# power.net
KiCad netlist of a schematic drawn in Altium Designer
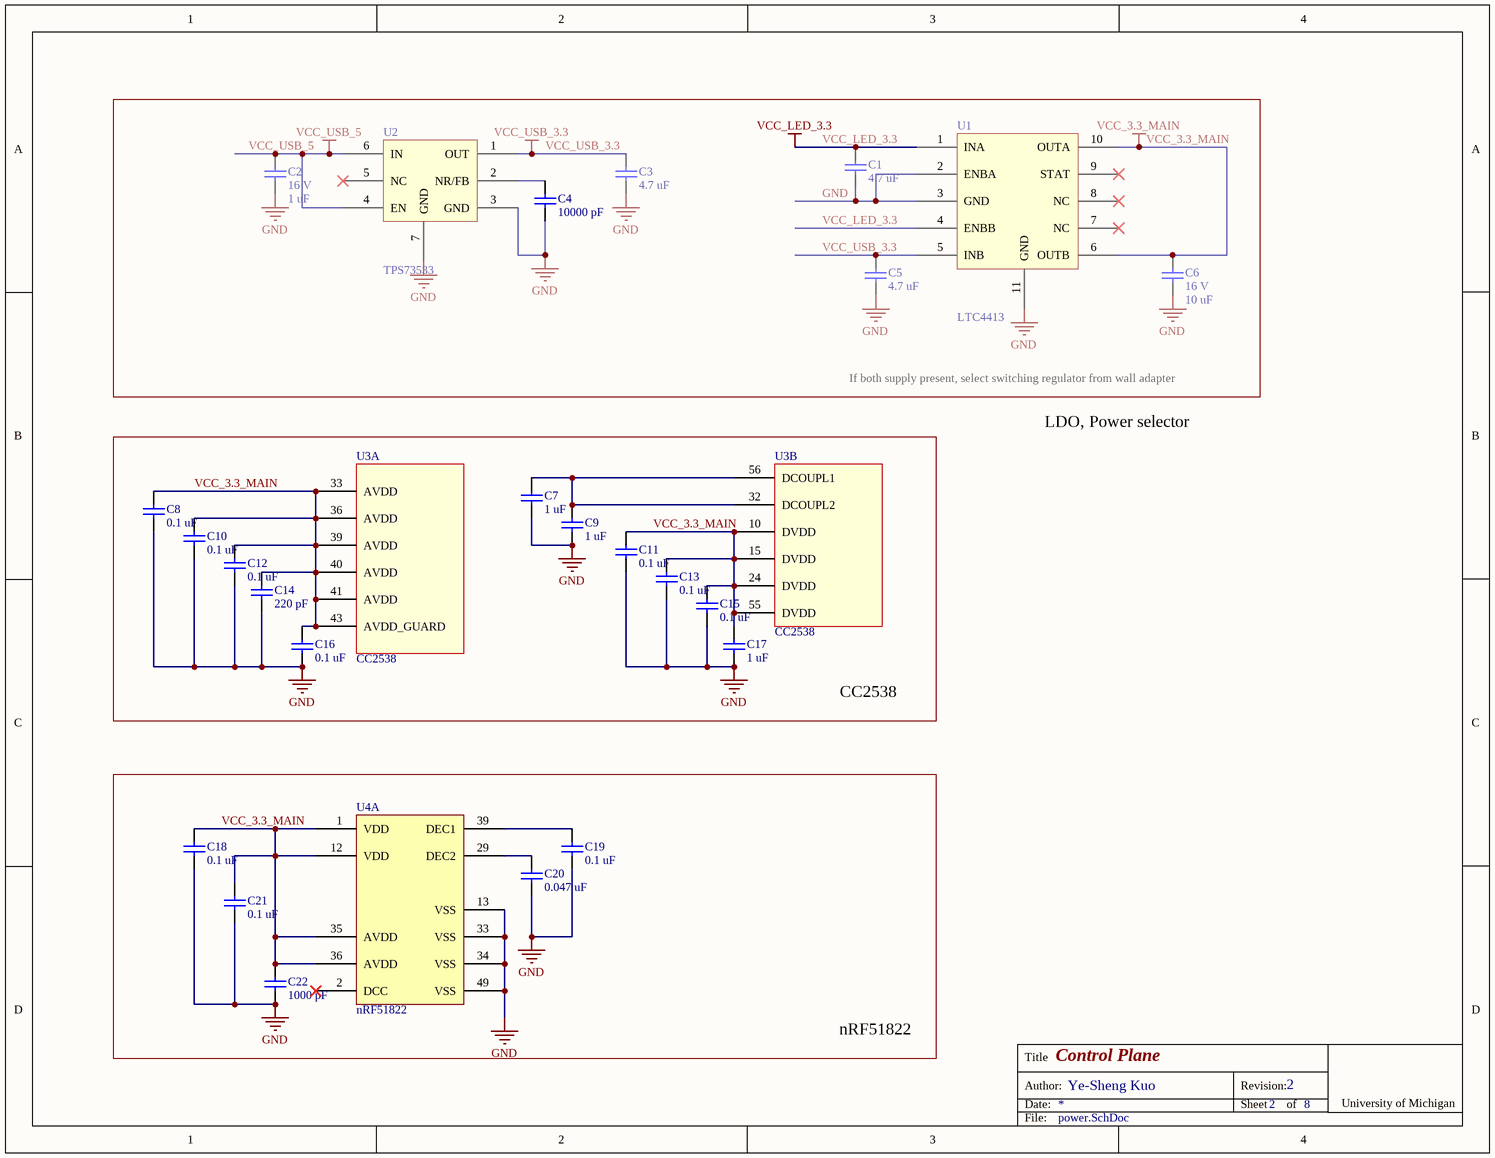
[diagram p0: power.SchDoc]

(export (version "E")
  (design (tool "Eeschema 10.0.6"))
  (components
    (comp (ref "C1")
      (value "4.7 uF")
      (footprint "0603")
      (description "Ceramic capacitor, 4.7u, 10V, 0603 package")
      (fields (field (name "TOLERANCE") "20%") (field (name "Comment") "Ceramic capacitor"))
      (libsource (lib "rlc") (part "C_4.7u_10V_0603_ceramic"))
    )
    (comp (ref "C2")
      (value "1 uF")
      (footprint "0603")
      (description "Ceramic capacitor, 1 uF, 16 V, 0603 package")
      (fields
        (field (name "TOLERANCE") "10%")
        (field (name "VOLTAGE RATED") "16 V")
        (field (name "Comment") "Ceramic capacitor")
      )
      (libsource (lib "rlc") (part "C_1u_16V_0603_ceramic"))
    )
    (comp (ref "C3")
      (value "4.7 uF")
      (footprint "0603")
      (description "Ceramic capacitor, 4.7u, 10V, 0603 package")
      (fields (field (name "TOLERANCE") "20%") (field (name "Comment") "Ceramic capacitor"))
      (libsource (lib "rlc") (part "C_4.7u_10V_0603_ceramic"))
    )
    (comp (ref "C4")
      (value "10000 pF")
      (footprint "0402")
      (description "Ceramic capacitor, 10000 pF, 16 V, 0402 package")
      (fields (field (name "TOLERANCE") "10%") (field (name "Comment") "Ceramic capacitor"))
      (libsource (lib "rlc") (part "C_10000p_16V_0402_ceramic"))
    )
    (comp (ref "C5")
      (value "4.7 uF")
      (footprint "0603")
      (description "Ceramic capacitor, 4.7u, 10V, 0603 package")
      (fields (field (name "TOLERANCE") "20%") (field (name "Comment") "Ceramic capacitor"))
      (libsource (lib "rlc") (part "C_4.7u_10V_0603_ceramic"))
    )
    (comp (ref "C6")
      (value "10 uF")
      (footprint "0603")
      (description "Ceramic capacitor, 10 uF, 16 V, 0603 package")
      (fields
        (field (name "TOLERANCE") "20%")
        (field (name "VOLTAGE RATED") "16 V")
        (field (name "Comment") "Ceramic capacitor")
      )
      (libsource (lib "rlc") (part "C_10u_16V_0603_ceramic"))
    )
    (comp (ref "C7")
      (value "1 uF")
      (footprint "0402")
      (description "Ceramic capacitor, 1 uF, 16V, 0402 package")
      (fields (field (name "TOLERANCE") "10%") (field (name "Comment") "Ceramic capacitor"))
      (libsource (lib "rlc") (part "C_1u_16V_0402_ceramic"))
    )
    (comp (ref "C8")
      (value "0.1 uF")
      (footprint "0402")
      (description "Ceramic capacitor, 0.1u, 0402 package")
      (fields (field (name "TOLERANCE") "10%") (field (name "Comment") "Ceramic capacitor"))
      (libsource (lib "rlc") (part "C_0.1u_10V_0402_ceramic"))
    )
    (comp (ref "C9")
      (value "1 uF")
      (footprint "0402")
      (description "Ceramic capacitor, 1 uF, 16V, 0402 package")
      (fields (field (name "TOLERANCE") "10%") (field (name "Comment") "Ceramic capacitor"))
      (libsource (lib "rlc") (part "C_1u_16V_0402_ceramic"))
    )
    (comp (ref "C10")
      (value "0.1 uF")
      (footprint "0402")
      (description "Ceramic capacitor, 0.1u, 0402 package")
      (fields (field (name "TOLERANCE") "10%") (field (name "Comment") "Ceramic capacitor"))
      (libsource (lib "rlc") (part "C_0.1u_10V_0402_ceramic"))
    )
    (comp (ref "C11")
      (value "0.1 uF")
      (footprint "0402")
      (description "Ceramic capacitor, 0.1u, 0402 package")
      (fields (field (name "TOLERANCE") "10%") (field (name "Comment") "Ceramic capacitor"))
      (libsource (lib "rlc") (part "C_0.1u_10V_0402_ceramic"))
    )
    (comp (ref "C12")
      (value "0.1 uF")
      (footprint "0402")
      (description "Ceramic capacitor, 0.1u, 0402 package")
      (fields (field (name "TOLERANCE") "10%") (field (name "Comment") "Ceramic capacitor"))
      (libsource (lib "rlc") (part "C_0.1u_10V_0402_ceramic"))
    )
    (comp (ref "C13")
      (value "0.1 uF")
      (footprint "0402")
      (description "Ceramic capacitor, 0.1u, 0402 package")
      (fields (field (name "TOLERANCE") "10%") (field (name "Comment") "Ceramic capacitor"))
      (libsource (lib "rlc") (part "C_0.1u_10V_0402_ceramic"))
    )
    (comp (ref "C14")
      (value "220 pF")
      (footprint "0402")
      (description "Ceramic capacitor, 220 pF, 0402 package")
      (fields (field (name "TOLERANCE") "10%") (field (name "Comment") "Ceramic capacitor"))
      (libsource (lib "rlc") (part "C_220p_50V_0402_ceramic"))
    )
    (comp (ref "C15")
      (value "0.1 uF")
      (footprint "0402")
      (description "Ceramic capacitor, 0.1u, 0402 package")
      (fields (field (name "TOLERANCE") "10%") (field (name "Comment") "Ceramic capacitor"))
      (libsource (lib "rlc") (part "C_0.1u_10V_0402_ceramic"))
    )
    (comp (ref "C16")
      (value "0.1 uF")
      (footprint "0402")
      (description "Ceramic capacitor, 0.1u, 0402 package")
      (fields (field (name "TOLERANCE") "10%") (field (name "Comment") "Ceramic capacitor"))
      (libsource (lib "rlc") (part "C_0.1u_10V_0402_ceramic"))
    )
    (comp (ref "C17")
      (value "1 uF")
      (footprint "0402")
      (description "Ceramic capacitor, 1 uF, 16V, 0402 package")
      (fields (field (name "TOLERANCE") "10%") (field (name "Comment") "Ceramic capacitor"))
      (libsource (lib "rlc") (part "C_1u_16V_0402_ceramic"))
    )
    (comp (ref "C18")
      (value "0.1 uF")
      (footprint "0402")
      (description "Ceramic capacitor, 0.1u, 0402 package")
      (fields (field (name "TOLERANCE") "10%") (field (name "Comment") "Ceramic capacitor"))
      (libsource (lib "rlc") (part "C_0.1u_10V_0402_ceramic"))
    )
    (comp (ref "C19")
      (value "0.1 uF")
      (footprint "0402")
      (description "Ceramic capacitor, 0.1u, 0402 package")
      (fields (field (name "TOLERANCE") "10%") (field (name "Comment") "Ceramic capacitor"))
      (libsource (lib "rlc") (part "C_0.1u_10V_0402_ceramic"))
    )
    (comp (ref "C20")
      (value "0.047 uF")
      (footprint "0402")
      (description "Ceramic capacitor, 0.047u, 16V, 0402 package")
      (fields (field (name "TOLERANCE") "10%") (field (name "Comment") "Ceramic capacitor"))
      (libsource (lib "rlc") (part "C_0.047u_16V_0402_ceramic"))
    )
    (comp (ref "C21")
      (value "0.1 uF")
      (footprint "0402")
      (description "Ceramic capacitor, 0.1u, 0402 package")
      (fields (field (name "TOLERANCE") "10%") (field (name "Comment") "Ceramic capacitor"))
      (libsource (lib "rlc") (part "C_0.1u_10V_0402_ceramic"))
    )
    (comp (ref "C22")
      (value "1000 pF")
      (footprint "0402")
      (description "Ceramic capacitor, 1000 pF, 0402 package")
      (fields (field (name "TOLERANCE") "10%") (field (name "Comment") "Ceramic capacitor"))
      (libsource (lib "rlc") (part "C_1000p_50V_0402_ceramic"))
    )
    (comp (ref "U1")
      (value "LTC4413")
      (footprint "DFN-10")
      (description "Dual 2.6A, 2.5V to 5.5V,  Ideal Diodes in 3mm × 3mm DFN")
      (libsource (lib "sdl") (part "LTC4413"))
    )
    (comp (ref "U2")
      (value "TPS73533")
      (footprint "SON-6")
      (description "500mA, Low Quiescent Current, Ultra-Low Noise, High PSRR  Low-Dropout Linear Regulator")
      (libsource (lib "voltage_regulators") (part "TPS73533"))
    )
    (comp (ref "U3")
      (value "CC2538")
      (footprint "QFN56")
      (description "A Powerful System-On-Chip for 2.4-GHz IEEE 802.15.4, 6LoWPAN  and ZigBee Applications")
      (libsource (lib "sdl") (part "CC2538"))
    )
    (comp (ref "U4")
      (value "nRF51822")
      (footprint "QFN-48")
      (description "Multiprotocol Bluetooth® low energy/2.4 GHz RF System on Chip")
      (libsource (lib "sdl") (part "nRF51822"))
    )
  )
  (nets
    (net (code "1") (name "GND") (class "Default")
      (node (ref "C1") (pin "2") (pintype "passive"))
      (node (ref "C10") (pin "2") (pintype "passive"))
      (node (ref "C11") (pin "2") (pintype "passive"))
      (node (ref "C12") (pin "2") (pintype "passive"))
      (node (ref "C13") (pin "2") (pintype "passive"))
      (node (ref "C14") (pin "2") (pintype "passive"))
      (node (ref "C15") (pin "2") (pintype "passive"))
      (node (ref "C16") (pin "2") (pintype "passive"))
      (node (ref "C17") (pin "2") (pintype "passive"))
      (node (ref "C18") (pin "2") (pintype "passive"))
      (node (ref "C19") (pin "2") (pintype "passive"))
      (node (ref "C2") (pin "2") (pintype "passive"))
      (node (ref "C20") (pin "2") (pintype "passive"))
      (node (ref "C21") (pin "2") (pintype "passive"))
      (node (ref "C22") (pin "2") (pintype "passive"))
      (node (ref "C3") (pin "2") (pintype "passive"))
      (node (ref "C4") (pin "2") (pintype "passive"))
      (node (ref "C5") (pin "2") (pintype "passive"))
      (node (ref "C6") (pin "2") (pintype "passive"))
      (node (ref "C7") (pin "2") (pintype "passive"))
      (node (ref "C8") (pin "2") (pintype "passive"))
      (node (ref "C9") (pin "2") (pintype "passive"))
      (node (ref "U1") (pin "11") (pinfunction "GND_11") (pintype "passive"))
      (node (ref "U1") (pin "2") (pinfunction "ENBA_2") (pintype "passive"))
      (node (ref "U1") (pin "3") (pinfunction "GND_3") (pintype "passive"))
      (node (ref "U2") (pin "3") (pinfunction "GND_3") (pintype "passive"))
      (node (ref "U2") (pin "7") (pinfunction "GND_7") (pintype "passive"))
      (node (ref "U4") (pin "13") (pinfunction "VSS_13") (pintype "passive"))
      (node (ref "U4") (pin "33") (pinfunction "VSS_33") (pintype "passive"))
      (node (ref "U4") (pin "34") (pinfunction "VSS_34") (pintype "passive"))
      (node (ref "U4") (pin "49") (pinfunction "VSS_49") (pintype "passive"))
    )
    (net (code "2") (name "Net-(U2-NR{slash}FB)") (class "Default")
      (node (ref "C4") (pin "1") (pintype "passive"))
      (node (ref "U2") (pin "2") (pinfunction "NR/FB_2") (pintype "passive"))
    )
    (net (code "3") (name "Net-(U3B-DCOUPL1)") (class "Default")
      (node (ref "C7") (pin "1") (pintype "passive"))
      (node (ref "C9") (pin "1") (pintype "passive"))
      (node (ref "U3") (pin "32") (pinfunction "DCOUPL2_32") (pintype "power_in"))
      (node (ref "U3") (pin "56") (pinfunction "DCOUPL1_56") (pintype "power_in"))
    )
    (net (code "4") (name "Net-(U4A-DEC1)") (class "Default")
      (node (ref "C19") (pin "1") (pintype "passive"))
      (node (ref "U4") (pin "39") (pinfunction "DEC1_39") (pintype "passive"))
    )
    (net (code "5") (name "Net-(U4A-DEC2)") (class "Default")
      (node (ref "C20") (pin "1") (pintype "passive"))
      (node (ref "U4") (pin "29") (pinfunction "DEC2_29") (pintype "passive"))
    )
    (net (code "6") (name "VCC_3.3_MAIN") (class "Default")
      (node (ref "C10") (pin "1") (pintype "passive"))
      (node (ref "C11") (pin "1") (pintype "passive"))
      (node (ref "C12") (pin "1") (pintype "passive"))
      (node (ref "C13") (pin "1") (pintype "passive"))
      (node (ref "C14") (pin "1") (pintype "passive"))
      (node (ref "C15") (pin "1") (pintype "passive"))
      (node (ref "C16") (pin "1") (pintype "passive"))
      (node (ref "C17") (pin "1") (pintype "passive"))
      (node (ref "C18") (pin "1") (pintype "passive"))
      (node (ref "C21") (pin "1") (pintype "passive"))
      (node (ref "C22") (pin "1") (pintype "passive"))
      (node (ref "C6") (pin "1") (pintype "passive"))
      (node (ref "C8") (pin "1") (pintype "passive"))
      (node (ref "U1") (pin "10") (pinfunction "OUTA_10") (pintype "passive"))
      (node (ref "U1") (pin "6") (pinfunction "OUTB_6") (pintype "passive"))
      (node (ref "U3") (pin "10") (pinfunction "DVDD_10") (pintype "power_in"))
      (node (ref "U3") (pin "15") (pinfunction "DVDD_15") (pintype "power_in"))
      (node (ref "U3") (pin "24") (pinfunction "DVDD_24") (pintype "power_in"))
      (node (ref "U3") (pin "33") (pinfunction "AVDD_33") (pintype "power_in"))
      (node (ref "U3") (pin "36") (pinfunction "AVDD_36") (pintype "power_in"))
      (node (ref "U3") (pin "39") (pinfunction "AVDD_39") (pintype "power_in"))
      (node (ref "U3") (pin "40") (pinfunction "AVDD_40") (pintype "power_in"))
      (node (ref "U3") (pin "41") (pinfunction "AVDD_41") (pintype "power_in"))
      (node (ref "U3") (pin "43") (pinfunction "AVDD_GUARD_43") (pintype "power_in"))
      (node (ref "U3") (pin "55") (pinfunction "DVDD_55") (pintype "power_in"))
      (node (ref "U4") (pin "1") (pinfunction "VDD_1") (pintype "passive"))
      (node (ref "U4") (pin "12") (pinfunction "VDD_12") (pintype "passive"))
      (node (ref "U4") (pin "35") (pinfunction "AVDD_35") (pintype "passive"))
      (node (ref "U4") (pin "36") (pinfunction "AVDD_36") (pintype "passive"))
    )
    (net (code "7") (name "VCC_LED_3.3") (class "Default")
      (node (ref "C1") (pin "1") (pintype "passive"))
      (node (ref "U1") (pin "1") (pinfunction "INA_1") (pintype "passive"))
      (node (ref "U1") (pin "4") (pinfunction "ENBB_4") (pintype "passive"))
    )
    (net (code "8") (name "VCC_USB_3.3") (class "Default")
      (node (ref "C3") (pin "1") (pintype "passive"))
      (node (ref "C5") (pin "1") (pintype "passive"))
      (node (ref "U1") (pin "5") (pinfunction "INB_5") (pintype "passive"))
      (node (ref "U2") (pin "1") (pinfunction "OUT_1") (pintype "passive"))
    )
    (net (code "9") (name "VCC_USB_5") (class "Default")
      (node (ref "C2") (pin "1") (pintype "passive"))
      (node (ref "U2") (pin "4") (pinfunction "EN_4") (pintype "passive"))
      (node (ref "U2") (pin "6") (pinfunction "IN_6") (pintype "passive"))
    )
    (net (code "10") (name "unconnected-(U1-NC-Pad7)") (class "Default")
      (node (ref "U1") (pin "7") (pinfunction "NC_7") (pintype "passive+no_connect"))
    )
    (net (code "11") (name "unconnected-(U1-NC-Pad8)") (class "Default")
      (node (ref "U1") (pin "8") (pinfunction "NC_8") (pintype "passive+no_connect"))
    )
    (net (code "12") (name "unconnected-(U1-STAT-Pad9)") (class "Default")
      (node (ref "U1") (pin "9") (pinfunction "STAT_9") (pintype "passive+no_connect"))
    )
    (net (code "13") (name "unconnected-(U2-NC-Pad5)") (class "Default")
      (node (ref "U2") (pin "5") (pinfunction "NC_5") (pintype "passive+no_connect"))
    )
    (net (code "14") (name "unconnected-(U4A-DCC-Pad2)") (class "Default")
      (node (ref "U4") (pin "2") (pinfunction "DCC_2") (pintype "passive+no_connect"))
    )
  )
)
